# Cypress.net
KiCad netlist of a schematic drawn in Altium Designer
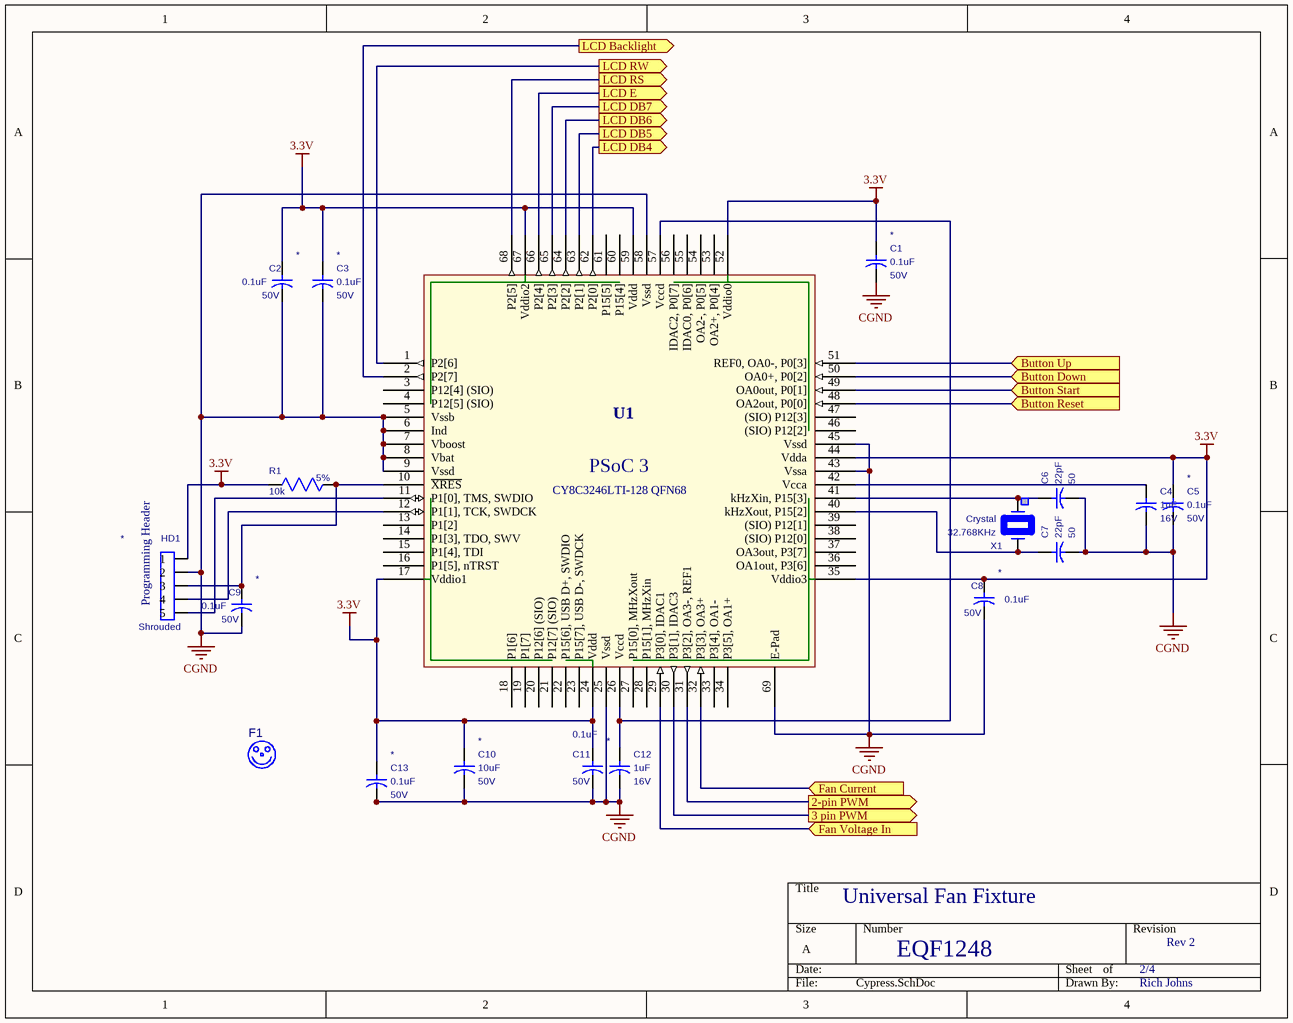
[diagram p0: Cypress.SchDoc]

(export (version "E")
  (design (tool "Eeschema 10.0.6"))
  (components
    (comp (ref "C1")
      (value "0.1uF")
      (footprint "0603")
      (fields
        (field (name "DNS") "*")
        (field (name "VOLTAGE") "50V")
        (field (name "TOLERANCE") "+/- 20%")
        (field (name "Comment") "CAP_NON_POLAR_SMT")
        (field (name "CHECKEDBY") "Sam Rhoufiry")
        (field (name "CREATEDBY") "Mike Tyger")
        (field (name "LASTUPDATEDBY") "Mike Tyger")
      )
      (libsource (lib "bome") (part "CAP_NON_POLAR_SMT"))
    )
    (comp (ref "C2")
      (value "0.1uF")
      (footprint "0603")
      (fields
        (field (name "DNS") "*")
        (field (name "VOLTAGE") "50V")
        (field (name "TOLERANCE") "+/- 20%")
        (field (name "Comment") "CAP_NON_POLAR_SMT")
        (field (name "CHECKEDBY") "Sam Rhoufiry")
        (field (name "CREATEDBY") "Mike Tyger")
        (field (name "LASTUPDATEDBY") "Mike Tyger")
      )
      (libsource (lib "bome") (part "CAP_NON_POLAR_SMT"))
    )
    (comp (ref "C3")
      (value "0.1uF")
      (footprint "0603")
      (fields
        (field (name "DNS") "*")
        (field (name "VOLTAGE") "50V")
        (field (name "TOLERANCE") "+/- 20%")
        (field (name "Comment") "CAP_NON_POLAR_SMT")
        (field (name "CHECKEDBY") "Sam Rhoufiry")
        (field (name "CREATEDBY") "Mike Tyger")
        (field (name "LASTUPDATEDBY") "Mike Tyger")
      )
      (libsource (lib "bome") (part "CAP_NON_POLAR_SMT"))
    )
    (comp (ref "C4")
      (value "1uF")
      (footprint "0603")
      (fields
        (field (name "TOLERANCE") "+/- 10%")
        (field (name "VOLTAGE") "16V")
        (field (name "Comment") "1.0uF_0603_16V")
        (field (name "CHECKEDBY") "gdeguzman")
        (field (name "LASTUPDATEDBY") "Rui Zhang")
      )
      (libsource (lib "bome") (part "1.0uF_0603_16V"))
    )
    (comp (ref "C5")
      (value "0.1uF")
      (footprint "0603")
      (fields
        (field (name "DNS") "*")
        (field (name "VOLTAGE") "50V")
        (field (name "TOLERANCE") "+/- 20%")
        (field (name "Comment") "CAP_NON_POLAR_SMT")
        (field (name "CHECKEDBY") "Sam Rhoufiry")
        (field (name "CREATEDBY") "Mike Tyger")
        (field (name "LASTUPDATEDBY") "Mike Tyger")
      )
      (libsource (lib "bome") (part "CAP_NON_POLAR_SMT"))
    )
    (comp (ref "C6")
      (value "22pF")
      (footprint "0603")
      (description "Capacitor, 22pF, 50, Ceramic, NPO, +/-5%, Non-Polar, 0603, 2, Kemet:C0603C220J5GACTU or equivalent")
      (fields
        (field (name "TOLERANCE") "+/-5%")
        (field (name "VOLTAGE") "50")
        (field (name "Comment") "22pF_0603")
        (field (name "CHECKEDBY") "gdeguzman")
        (field (name "LASTUPDATEDBY") "Michael Angeli")
      )
      (libsource (lib "bome") (part "22pF_0603"))
    )
    (comp (ref "C7")
      (value "22pF")
      (footprint "0603")
      (description "Capacitor, 22pF, 50, Ceramic, NPO, +/-5%, Non-Polar, 0603, 2, Kemet:C0603C220J5GACTU or equivalent")
      (fields
        (field (name "TOLERANCE") "+/-5%")
        (field (name "VOLTAGE") "50")
        (field (name "Comment") "22pF_0603")
        (field (name "CHECKEDBY") "gdeguzman")
        (field (name "LASTUPDATEDBY") "Michael Angeli")
      )
      (libsource (lib "bome") (part "22pF_0603"))
    )
    (comp (ref "C8")
      (value "0.1uF")
      (footprint "0603")
      (fields
        (field (name "DNS") "*")
        (field (name "VOLTAGE") "50V")
        (field (name "TOLERANCE") "+/- 20%")
        (field (name "Comment") "CAP_NON_POLAR_SMT")
        (field (name "CHECKEDBY") "Sam Rhoufiry")
        (field (name "CREATEDBY") "Mike Tyger")
        (field (name "LASTUPDATEDBY") "Mike Tyger")
      )
      (libsource (lib "bome") (part "CAP_NON_POLAR_SMT"))
    )
    (comp (ref "C9")
      (value "0.1uF")
      (footprint "0603")
      (fields
        (field (name "DNS") "*")
        (field (name "VOLTAGE") "50V")
        (field (name "TOLERANCE") "+/- 20%")
        (field (name "Comment") "CAP_NON_POLAR_SMT")
        (field (name "CHECKEDBY") "Sam Rhoufiry")
        (field (name "CREATEDBY") "Mike Tyger")
        (field (name "LASTUPDATEDBY") "Mike Tyger")
      )
      (libsource (lib "bome") (part "CAP_NON_POLAR_SMT"))
    )
    (comp (ref "C10")
      (value "10uF")
      (footprint "1206")
      (fields
        (field (name "DNS") "*")
        (field (name "VOLTAGE") "50V")
        (field (name "TOLERANCE") "+/- 20%")
        (field (name "Comment") "CAP_NON_POLAR_SMT")
        (field (name "CHECKEDBY") "Sam Rhoufiry")
        (field (name "CREATEDBY") "Mike Tyger")
        (field (name "LASTUPDATEDBY") "Mike Tyger")
      )
      (libsource (lib "bome") (part "CAP_NON_POLAR_SMT"))
    )
    (comp (ref "C11")
      (value "0.1uF")
      (footprint "0603")
      (fields
        (field (name "DNS") "*")
        (field (name "VOLTAGE") "50V")
        (field (name "TOLERANCE") "+/- 20%")
        (field (name "Comment") "CAP_NON_POLAR_SMT")
        (field (name "CHECKEDBY") "Sam Rhoufiry")
        (field (name "CREATEDBY") "Mike Tyger")
        (field (name "LASTUPDATEDBY") "Mike Tyger")
      )
      (libsource (lib "bome") (part "CAP_NON_POLAR_SMT"))
    )
    (comp (ref "C12")
      (value "1uF")
      (footprint "0603")
      (fields
        (field (name "TOLERANCE") "+/- 10%")
        (field (name "VOLTAGE") "16V")
        (field (name "Comment") "1.0uF_0603_16V")
        (field (name "CHECKEDBY") "gdeguzman")
        (field (name "LASTUPDATEDBY") "Rui Zhang")
      )
      (libsource (lib "bome") (part "1.0uF_0603_16V"))
    )
    (comp (ref "C13")
      (value "0.1uF")
      (footprint "0603")
      (fields
        (field (name "DNS") "*")
        (field (name "VOLTAGE") "50V")
        (field (name "TOLERANCE") "+/- 20%")
        (field (name "Comment") "CAP_NON_POLAR_SMT")
        (field (name "CHECKEDBY") "Sam Rhoufiry")
        (field (name "CREATEDBY") "Mike Tyger")
        (field (name "LASTUPDATEDBY") "Mike Tyger")
      )
      (libsource (lib "bome") (part "CAP_NON_POLAR_SMT"))
    )
    (comp (ref "F1")
      (value "FIDUCIAL_SMILEY")
      (footprint "FIDUCIAL_SMILEY")
      (description "Fiducial, Smiley, PCB reference point, not a component")
      (fields (field (name "CREATEDBY") "Mike Tyger") (field (name "LASTUPDATEDBY") "Michael Angeli"))
      (libsource (lib "bome") (part "FIDUCIAL_SMILEY"))
    )
    (comp (ref "HD1")
      (value "HDR5PIN100SHRD")
      (footprint "HDR5PIN100SHRD")
      (description "Header, 0.100 in., 5 pin Pins, Shrouded, AMP: 644486-5")
      (fields
        (field (name "DNS") "*")
        (field (name "HEADERTYPE") "Shrouded")
        (field (name "CHECKEDBY") "Michael Angeli")
      )
      (libsource (lib "bome") (part "HDR5PIN100SHRD"))
    )
    (comp (ref "R1")
      (value "10k")
      (footprint "RC0603REFLOW-IPC")
      (description "Resistor, 18, ThickFilm, 5%, 0603, 1/8W, Any")
      (fields
        (field (name "TOLERANCE") "5%")
        (field (name "Comment") "R0603REFLOW_5%_1/8WATT")
        (field (name "CHECKEDBY") "*")
      )
      (libsource (lib "bome") (part "R0603REFLOW_5%_1/8WATT"))
    )
    (comp (ref "U1")
      (value "CY8C3246LTI-128 QFN68")
      (footprint "PSoC 3 and 5LP:QFN68_8x8-MD")
      (description "CY8C3xxxLTx-xxx 68 pin QFN")
      (fields (field (name "MFG") "Cypress"))
      (libsource (lib "PSoC 3") (part "CY8C3xxxLTx-xxx QFN68"))
    )
    (comp (ref "X1")
      (value "32.768KHZ_CRYSTAL")
      (footprint ".03_Small_Footprint_CRYSTAL")
      (description "Xtal, 0.7 mm, Cylinder, 2, Crystal, 32.768KHz, ECS: ECS-.327-12.5-13;Alternates require approval")
      (fields
        (field (name "FREQUENCY") "32.768KHz")
        (field (name "XTALTYPE") "Crystal")
        (field (name "CHECKEDBY") "Sam Rhoufiry")
      )
      (libsource (lib "bome") (part "32.768KHZ_CRYSTAL"))
    )
  )
  (nets
    (net (code "1") (name "/2-pin PWM") (class "Default")
      (node (ref "U1") (pin "31") (pinfunction "P3[2],_OA3-,_REF1_31") (pintype "output"))
    )
    (net (code "2") (name "/3 pin PWM") (class "Default")
      (node (ref "U1") (pin "30") (pinfunction "P3[1],_IDAC3_30") (pintype "output"))
    )
    (net (code "3") (name "/Button Down") (class "Default")
      (node (ref "U1") (pin "50") (pinfunction "OA0+,_P0[2]_50") (pintype "input"))
    )
    (net (code "4") (name "/Button Reset") (class "Default")
      (node (ref "U1") (pin "48") (pinfunction "OA2out,_P0[0]_48") (pintype "input"))
    )
    (net (code "5") (name "/Button Start") (class "Default")
      (node (ref "U1") (pin "49") (pinfunction "OA0out,_P0[1]_49") (pintype "input"))
    )
    (net (code "6") (name "/Button Up") (class "Default")
      (node (ref "U1") (pin "51") (pinfunction "REF0,_OA0-,_P0[3]_51") (pintype "input"))
    )
    (net (code "7") (name "/Fan Current") (class "Default")
      (node (ref "U1") (pin "32") (pinfunction "P3[3],_OA3+_32") (pintype "input"))
    )
    (net (code "8") (name "/Fan Voltage In") (class "Default")
      (node (ref "U1") (pin "29") (pinfunction "P3[0],_IDAC1_29") (pintype "input"))
    )
    (net (code "9") (name "/LCD Backlight") (class "Default")
      (node (ref "U1") (pin "2") (pinfunction "P2[7]_2") (pintype "output"))
    )
    (net (code "10") (name "/LCD DB4") (class "Default")
      (node (ref "U1") (pin "62") (pinfunction "P2[0]_62") (pintype "output"))
    )
    (net (code "11") (name "/LCD DB5") (class "Default")
      (node (ref "U1") (pin "63") (pinfunction "P2[1]_63") (pintype "output"))
    )
    (net (code "12") (name "/LCD DB6") (class "Default")
      (node (ref "U1") (pin "64") (pinfunction "P2[2]_64") (pintype "output"))
    )
    (net (code "13") (name "/LCD DB7") (class "Default")
      (node (ref "U1") (pin "65") (pinfunction "P2[3]_65") (pintype "output"))
    )
    (net (code "14") (name "/LCD E") (class "Default")
      (node (ref "U1") (pin "66") (pinfunction "P2[4]_66") (pintype "output"))
    )
    (net (code "15") (name "/LCD RS") (class "Default")
      (node (ref "U1") (pin "68") (pinfunction "P2[5]_68") (pintype "output"))
    )
    (net (code "16") (name "/LCD RW") (class "Default")
      (node (ref "U1") (pin "1") (pinfunction "P2[6]_1") (pintype "output"))
    )
    (net (code "17") (name "3.3V") (class "Default")
      (node (ref "C1") (pin "1") (pinfunction "pin1_1") (pintype "passive"))
      (node (ref "C10") (pin "1") (pinfunction "pin1_1") (pintype "passive"))
      (node (ref "C11") (pin "1") (pinfunction "pin1_1") (pintype "passive"))
      (node (ref "C13") (pin "1") (pinfunction "pin1_1") (pintype "passive"))
      (node (ref "C2") (pin "1") (pinfunction "pin1_1") (pintype "passive"))
      (node (ref "C3") (pin "1") (pinfunction "pin1_1") (pintype "passive"))
      (node (ref "C5") (pin "1") (pinfunction "pin1_1") (pintype "passive"))
      (node (ref "C8") (pin "1") (pinfunction "pin1_1") (pintype "passive"))
      (node (ref "HD1") (pin "1") (pinfunction "1_1") (pintype "passive"))
      (node (ref "R1") (pin "2") (pinfunction "pin2_2") (pintype "passive"))
      (node (ref "U1") (pin "17") (pinfunction "Vddio1_17") (pintype "power_in"))
      (node (ref "U1") (pin "24") (pinfunction "Vddd_24") (pintype "power_in"))
      (node (ref "U1") (pin "35") (pinfunction "Vddio3_35") (pintype "power_in"))
      (node (ref "U1") (pin "44") (pinfunction "Vdda_44") (pintype "power_in"))
      (node (ref "U1") (pin "52") (pinfunction "Vddio0_52") (pintype "power_in"))
      (node (ref "U1") (pin "59") (pinfunction "Vddd_59") (pintype "power_in"))
      (node (ref "U1") (pin "67") (pinfunction "Vddio2_67") (pintype "power_in"))
    )
    (net (code "18") (name "CGND") (class "Default")
      (node (ref "C1") (pin "2") (pinfunction "pin2_2") (pintype "passive"))
      (node (ref "C10") (pin "2") (pinfunction "pin2_2") (pintype "passive"))
      (node (ref "C11") (pin "2") (pinfunction "pin2_2") (pintype "passive"))
      (node (ref "C12") (pin "2") (pinfunction "pin2_2") (pintype "passive"))
      (node (ref "C13") (pin "2") (pinfunction "pin2_2") (pintype "passive"))
      (node (ref "C2") (pin "2") (pinfunction "pin2_2") (pintype "passive"))
      (node (ref "C3") (pin "2") (pinfunction "pin2_2") (pintype "passive"))
      (node (ref "C4") (pin "2") (pinfunction "pin2_2") (pintype "passive"))
      (node (ref "C5") (pin "2") (pinfunction "pin2_2") (pintype "passive"))
      (node (ref "C6") (pin "2") (pinfunction "pin2_2") (pintype "passive"))
      (node (ref "C7") (pin "2") (pinfunction "pin2_2") (pintype "passive"))
      (node (ref "C8") (pin "2") (pinfunction "pin2_2") (pintype "passive"))
      (node (ref "C9") (pin "2") (pinfunction "pin2_2") (pintype "passive"))
      (node (ref "HD1") (pin "2") (pinfunction "2_2") (pintype "passive"))
      (node (ref "U1") (pin "25") (pinfunction "Vssd_25") (pintype "power_in"))
      (node (ref "U1") (pin "43") (pinfunction "Vssa_43") (pintype "passive"))
      (node (ref "U1") (pin "45") (pinfunction "Vssd_45") (pintype "passive"))
      (node (ref "U1") (pin "5") (pinfunction "Vssb_5") (pintype "power_in"))
      (node (ref "U1") (pin "58") (pinfunction "Vssd_58") (pintype "power_in"))
      (node (ref "U1") (pin "6") (pinfunction "Ind_6") (pintype "passive"))
      (node (ref "U1") (pin "69") (pinfunction "E-Pad_69") (pintype "power_in"))
      (node (ref "U1") (pin "7") (pinfunction "Vboost_7") (pintype "passive"))
      (node (ref "U1") (pin "8") (pinfunction "Vbat_8") (pintype "power_in"))
      (node (ref "U1") (pin "9") (pinfunction "Vssd_9") (pintype "power_in"))
    )
    (net (code "19") (name "Net-(C4-pin1)") (class "Default")
      (node (ref "C4") (pin "1") (pinfunction "pin1_1") (pintype "passive"))
      (node (ref "U1") (pin "42") (pinfunction "Vcca_42") (pintype "power_in"))
    )
    (net (code "20") (name "Net-(C6-pin1)") (class "Default")
      (node (ref "C6") (pin "1") (pinfunction "pin1_1") (pintype "passive"))
      (node (ref "U1") (pin "41") (pinfunction "kHzXin,_P15[3]_41") (pintype "passive"))
      (node (ref "X1") (pin "1") (pinfunction "1_1") (pintype "passive"))
    )
    (net (code "21") (name "Net-(C7-pin1)") (class "Default")
      (node (ref "C7") (pin "1") (pinfunction "pin1_1") (pintype "passive"))
      (node (ref "U1") (pin "40") (pinfunction "kHzXout,_P15[2]_40") (pintype "passive"))
      (node (ref "X1") (pin "2") (pinfunction "2_2") (pintype "passive"))
    )
    (net (code "22") (name "Net-(C9-pin1)") (class "Default")
      (node (ref "C9") (pin "1") (pinfunction "pin1_1") (pintype "passive"))
      (node (ref "HD1") (pin "3") (pinfunction "3_3") (pintype "passive"))
      (node (ref "R1") (pin "1") (pinfunction "pin1_1") (pintype "passive"))
      (node (ref "U1") (pin "10") (pinfunction "~{XRES}_10") (pintype "tri_state"))
    )
    (net (code "23") (name "Net-(C12-pin1)") (class "Default")
      (node (ref "C12") (pin "1") (pinfunction "pin1_1") (pintype "passive"))
      (node (ref "U1") (pin "26") (pinfunction "Vccd_26") (pintype "power_in"))
      (node (ref "U1") (pin "57") (pinfunction "Vccd_57") (pintype "power_in"))
    )
    (net (code "24") (name "Net-(U1-P1[0],_TMS,_SWDIO)") (class "Default")
      (node (ref "HD1") (pin "5") (pinfunction "5_5") (pintype "passive"))
      (node (ref "U1") (pin "11") (pinfunction "P1[0],_TMS,_SWDIO_11") (pintype "bidirectional"))
    )
    (net (code "25") (name "Net-(U1-P1[1],_TCK,_SWDCK)") (class "Default")
      (node (ref "HD1") (pin "4") (pinfunction "4_4") (pintype "passive"))
      (node (ref "U1") (pin "12") (pinfunction "P1[1],_TCK,_SWDCK_12") (pintype "bidirectional"))
    )
    (net (code "26") (name "unconnected-(HD1-Pad6)") (class "Default")
      (node (ref "HD1") (pin "6") (pintype "passive"))
    )
    (net (code "27") (name "unconnected-(U1-(SIO)_P12[0]-Pad38)") (class "Default")
      (node (ref "U1") (pin "38") (pinfunction "(SIO)_P12[0]_38") (pintype "passive"))
    )
    (net (code "28") (name "unconnected-(U1-(SIO)_P12[1]-Pad39)") (class "Default")
      (node (ref "U1") (pin "39") (pinfunction "(SIO)_P12[1]_39") (pintype "passive"))
    )
    (net (code "29") (name "unconnected-(U1-(SIO)_P12[2]-Pad46)") (class "Default")
      (node (ref "U1") (pin "46") (pinfunction "(SIO)_P12[2]_46") (pintype "passive"))
    )
    (net (code "30") (name "unconnected-(U1-(SIO)_P12[3]-Pad47)") (class "Default")
      (node (ref "U1") (pin "47") (pinfunction "(SIO)_P12[3]_47") (pintype "passive"))
    )
    (net (code "31") (name "unconnected-(U1-IDAC0,_P0[6]-Pad55)") (class "Default")
      (node (ref "U1") (pin "55") (pinfunction "IDAC0,_P0[6]_55") (pintype "passive"))
    )
    (net (code "32") (name "unconnected-(U1-IDAC2,_P0[7]-Pad56)") (class "Default")
      (node (ref "U1") (pin "56") (pinfunction "IDAC2,_P0[7]_56") (pintype "passive"))
    )
    (net (code "33") (name "unconnected-(U1-OA1out,_P3[6]-Pad36)") (class "Default")
      (node (ref "U1") (pin "36") (pinfunction "OA1out,_P3[6]_36") (pintype "passive"))
    )
    (net (code "34") (name "unconnected-(U1-OA2+,_P0[4]-Pad53)") (class "Default")
      (node (ref "U1") (pin "53") (pinfunction "OA2+,_P0[4]_53") (pintype "passive"))
    )
    (net (code "35") (name "unconnected-(U1-OA2-,_P0[5]-Pad54)") (class "Default")
      (node (ref "U1") (pin "54") (pinfunction "OA2-,_P0[5]_54") (pintype "passive"))
    )
    (net (code "36") (name "unconnected-(U1-OA3out,_P3[7]-Pad37)") (class "Default")
      (node (ref "U1") (pin "37") (pinfunction "OA3out,_P3[7]_37") (pintype "passive"))
    )
    (net (code "37") (name "unconnected-(U1-P1[2]-Pad13)") (class "Default")
      (node (ref "U1") (pin "13") (pinfunction "P1[2]_13") (pintype "passive"))
    )
    (net (code "38") (name "unconnected-(U1-P1[3],_TDO,_SWV-Pad14)") (class "Default")
      (node (ref "U1") (pin "14") (pinfunction "P1[3],_TDO,_SWV_14") (pintype "passive"))
    )
    (net (code "39") (name "unconnected-(U1-P1[4],_TDI-Pad15)") (class "Default")
      (node (ref "U1") (pin "15") (pinfunction "P1[4],_TDI_15") (pintype "passive"))
    )
    (net (code "40") (name "unconnected-(U1-P1[5],_nTRST-Pad16)") (class "Default")
      (node (ref "U1") (pin "16") (pinfunction "P1[5],_nTRST_16") (pintype "passive"))
    )
    (net (code "41") (name "unconnected-(U1-P1[6]-Pad18)") (class "Default")
      (node (ref "U1") (pin "18") (pinfunction "P1[6]_18") (pintype "passive"))
    )
    (net (code "42") (name "unconnected-(U1-P1[7]-Pad19)") (class "Default")
      (node (ref "U1") (pin "19") (pinfunction "P1[7]_19") (pintype "passive"))
    )
    (net (code "43") (name "unconnected-(U1-P3[4],_OA1--Pad33)") (class "Default")
      (node (ref "U1") (pin "33") (pinfunction "P3[4],_OA1-_33") (pintype "passive"))
    )
    (net (code "44") (name "unconnected-(U1-P3[5],_OA1+-Pad34)") (class "Default")
      (node (ref "U1") (pin "34") (pinfunction "P3[5],_OA1+_34") (pintype "passive"))
    )
    (net (code "45") (name "unconnected-(U1-P12[4]_(SIO)-Pad3)") (class "Default")
      (node (ref "U1") (pin "3") (pinfunction "P12[4]_(SIO)_3") (pintype "passive"))
    )
    (net (code "46") (name "unconnected-(U1-P12[5]_(SIO)-Pad4)") (class "Default")
      (node (ref "U1") (pin "4") (pinfunction "P12[5]_(SIO)_4") (pintype "passive"))
    )
    (net (code "47") (name "unconnected-(U1-P12[6]_(SIO)-Pad20)") (class "Default")
      (node (ref "U1") (pin "20") (pinfunction "P12[6]_(SIO)_20") (pintype "passive"))
    )
    (net (code "48") (name "unconnected-(U1-P12[7]_(SIO)-Pad21)") (class "Default")
      (node (ref "U1") (pin "21") (pinfunction "P12[7]_(SIO)_21") (pintype "passive"))
    )
    (net (code "49") (name "unconnected-(U1-P15[0],_MHzXout-Pad27)") (class "Default")
      (node (ref "U1") (pin "27") (pinfunction "P15[0],_MHzXout_27") (pintype "passive"))
    )
    (net (code "50") (name "unconnected-(U1-P15[1],_MHzXin-Pad28)") (class "Default")
      (node (ref "U1") (pin "28") (pinfunction "P15[1],_MHzXin_28") (pintype "passive"))
    )
    (net (code "51") (name "unconnected-(U1-P15[4]-Pad60)") (class "Default")
      (node (ref "U1") (pin "60") (pinfunction "P15[4]_60") (pintype "passive"))
    )
    (net (code "52") (name "unconnected-(U1-P15[5]-Pad61)") (class "Default")
      (node (ref "U1") (pin "61") (pinfunction "P15[5]_61") (pintype "passive"))
    )
    (net (code "53") (name "unconnected-(U1-P15[6],_USB_D+,_SWDIO-Pad22)") (class "Default")
      (node (ref "U1") (pin "22") (pinfunction "P15[6],_USB_D+,_SWDIO_22") (pintype "passive"))
    )
    (net (code "54") (name "unconnected-(U1-P15[7],_USB_D-,_SWDCK-Pad23)") (class "Default")
      (node (ref "U1") (pin "23") (pinfunction "P15[7],_USB_D-,_SWDCK_23") (pintype "passive"))
    )
  )
)
